# probatio_base.net
KiCad netlist of a schematic drawn in EAGLE
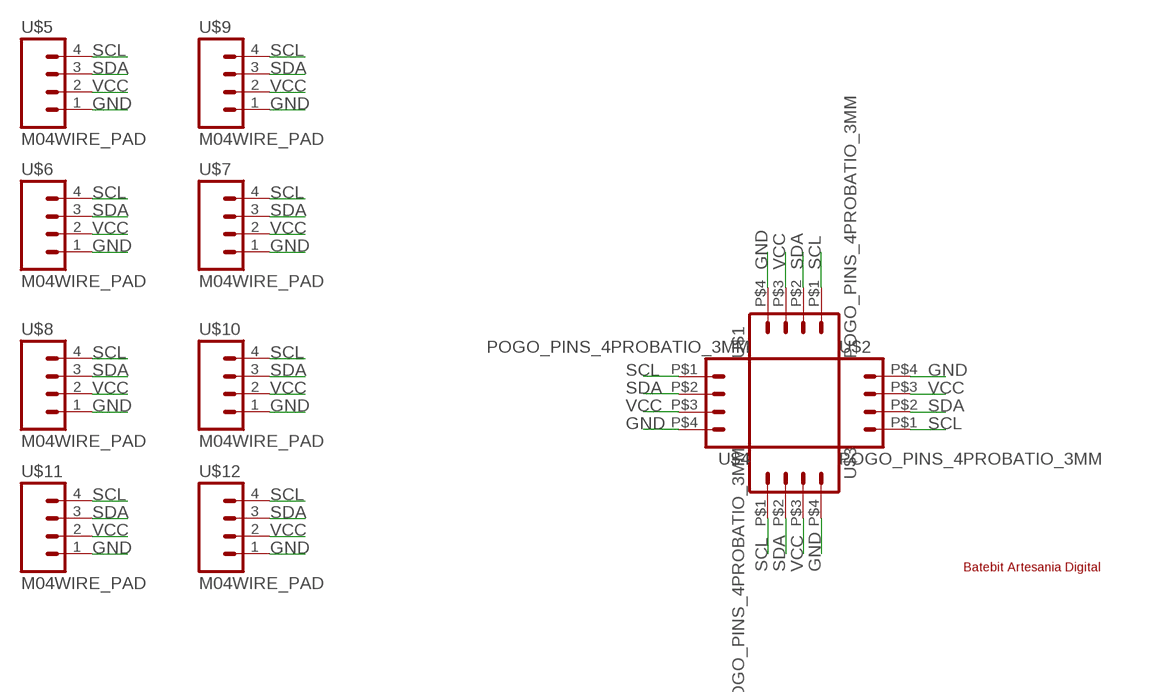
[diagram p0: schematic, sheet 1]

(export (version "E")
  (design (tool "Eeschema 10.0.6"))
  (components
    (comp (ref "U$1")
      (value "POGO_PINS_4PROBATIO_3MM")
      (footprint "eagle-import:POGO-PINS-4")
      (libsource (lib "eagle-import") (part "POGO_PINS_4PROBATIO_3MM"))
    )
    (comp (ref "U$2")
      (value "POGO_PINS_4PROBATIO_3MM")
      (footprint "eagle-import:POGO-PINS-4")
      (libsource (lib "eagle-import") (part "POGO_PINS_4PROBATIO_3MM"))
    )
    (comp (ref "U$3")
      (value "POGO_PINS_4PROBATIO_3MM")
      (footprint "eagle-import:POGO-PINS-4")
      (libsource (lib "eagle-import") (part "POGO_PINS_4PROBATIO_3MM"))
    )
    (comp (ref "U$4")
      (value "POGO_PINS_4PROBATIO_3MM")
      (footprint "eagle-import:POGO-PINS-4")
      (libsource (lib "eagle-import") (part "POGO_PINS_4PROBATIO_3MM"))
    )
    (comp (ref "U$5")
      (value "M04WIRE_PAD")
      (footprint "eagle-import:1X04_SMD")
      (libsource (lib "eagle-import") (part "M04WIRE_PAD"))
    )
    (comp (ref "U$6")
      (value "M04WIRE_PAD")
      (footprint "eagle-import:1X04_SMD")
      (libsource (lib "eagle-import") (part "M04WIRE_PAD"))
    )
    (comp (ref "U$7")
      (value "M04WIRE_PAD")
      (footprint "eagle-import:1X04_SMD")
      (libsource (lib "eagle-import") (part "M04WIRE_PAD"))
    )
    (comp (ref "U$8")
      (value "M04WIRE_PAD")
      (footprint "eagle-import:1X04_SMD")
      (libsource (lib "eagle-import") (part "M04WIRE_PAD"))
    )
    (comp (ref "U$9")
      (value "M04WIRE_PAD")
      (footprint "eagle-import:1X04_SMD")
      (libsource (lib "eagle-import") (part "M04WIRE_PAD"))
    )
    (comp (ref "U$10")
      (value "M04WIRE_PAD")
      (footprint "eagle-import:1X04_SMD")
      (libsource (lib "eagle-import") (part "M04WIRE_PAD"))
    )
    (comp (ref "U$11")
      (value "M04WIRE_PAD")
      (footprint "eagle-import:1X04_SMD")
      (libsource (lib "eagle-import") (part "M04WIRE_PAD"))
    )
    (comp (ref "U$12")
      (value "M04WIRE_PAD")
      (footprint "eagle-import:1X04_SMD")
      (libsource (lib "eagle-import") (part "M04WIRE_PAD"))
    )
    (comp (ref "U$13")
      (value "BATEBIT_PEQ")
      (footprint "eagle-import:BATEBIT_PEQ")
      (libsource (lib "eagle-import") (part "BATEBIT_PEQ"))
    )
  )
  (nets
    (net (code "1") (name "/GND") (class "Default")
      (node (ref "U$1") (pin "P$4") (pinfunction "4_P$4") (pintype "passive"))
      (node (ref "U$10") (pin "1") (pinfunction "1_1") (pintype "passive"))
      (node (ref "U$11") (pin "1") (pinfunction "1_1") (pintype "passive"))
      (node (ref "U$12") (pin "1") (pinfunction "1_1") (pintype "passive"))
      (node (ref "U$2") (pin "P$4") (pinfunction "4_P$4") (pintype "passive"))
      (node (ref "U$3") (pin "P$4") (pinfunction "4_P$4") (pintype "passive"))
      (node (ref "U$4") (pin "P$4") (pinfunction "4_P$4") (pintype "passive"))
      (node (ref "U$5") (pin "1") (pinfunction "1_1") (pintype "passive"))
      (node (ref "U$6") (pin "1") (pinfunction "1_1") (pintype "passive"))
      (node (ref "U$7") (pin "1") (pinfunction "1_1") (pintype "passive"))
      (node (ref "U$8") (pin "1") (pinfunction "1_1") (pintype "passive"))
      (node (ref "U$9") (pin "1") (pinfunction "1_1") (pintype "passive"))
    )
    (net (code "2") (name "/SCL") (class "Default")
      (node (ref "U$1") (pin "P$1") (pinfunction "1_P$1") (pintype "passive"))
      (node (ref "U$10") (pin "4") (pinfunction "4_4") (pintype "passive"))
      (node (ref "U$11") (pin "4") (pinfunction "4_4") (pintype "passive"))
      (node (ref "U$12") (pin "4") (pinfunction "4_4") (pintype "passive"))
      (node (ref "U$2") (pin "P$1") (pinfunction "1_P$1") (pintype "passive"))
      (node (ref "U$3") (pin "P$1") (pinfunction "1_P$1") (pintype "passive"))
      (node (ref "U$4") (pin "P$1") (pinfunction "1_P$1") (pintype "passive"))
      (node (ref "U$5") (pin "4") (pinfunction "4_4") (pintype "passive"))
      (node (ref "U$6") (pin "4") (pinfunction "4_4") (pintype "passive"))
      (node (ref "U$7") (pin "4") (pinfunction "4_4") (pintype "passive"))
      (node (ref "U$8") (pin "4") (pinfunction "4_4") (pintype "passive"))
      (node (ref "U$9") (pin "4") (pinfunction "4_4") (pintype "passive"))
    )
    (net (code "3") (name "/SDA") (class "Default")
      (node (ref "U$1") (pin "P$2") (pinfunction "2_P$2") (pintype "passive"))
      (node (ref "U$10") (pin "3") (pinfunction "3_3") (pintype "passive"))
      (node (ref "U$11") (pin "3") (pinfunction "3_3") (pintype "passive"))
      (node (ref "U$12") (pin "3") (pinfunction "3_3") (pintype "passive"))
      (node (ref "U$2") (pin "P$2") (pinfunction "2_P$2") (pintype "passive"))
      (node (ref "U$3") (pin "P$2") (pinfunction "2_P$2") (pintype "passive"))
      (node (ref "U$4") (pin "P$2") (pinfunction "2_P$2") (pintype "passive"))
      (node (ref "U$5") (pin "3") (pinfunction "3_3") (pintype "passive"))
      (node (ref "U$6") (pin "3") (pinfunction "3_3") (pintype "passive"))
      (node (ref "U$7") (pin "3") (pinfunction "3_3") (pintype "passive"))
      (node (ref "U$8") (pin "3") (pinfunction "3_3") (pintype "passive"))
      (node (ref "U$9") (pin "3") (pinfunction "3_3") (pintype "passive"))
    )
    (net (code "4") (name "/VCC") (class "Default")
      (node (ref "U$1") (pin "P$3") (pinfunction "3_P$3") (pintype "passive"))
      (node (ref "U$10") (pin "2") (pinfunction "2_2") (pintype "passive"))
      (node (ref "U$11") (pin "2") (pinfunction "2_2") (pintype "passive"))
      (node (ref "U$12") (pin "2") (pinfunction "2_2") (pintype "passive"))
      (node (ref "U$2") (pin "P$3") (pinfunction "3_P$3") (pintype "passive"))
      (node (ref "U$3") (pin "P$3") (pinfunction "3_P$3") (pintype "passive"))
      (node (ref "U$4") (pin "P$3") (pinfunction "3_P$3") (pintype "passive"))
      (node (ref "U$5") (pin "2") (pinfunction "2_2") (pintype "passive"))
      (node (ref "U$6") (pin "2") (pinfunction "2_2") (pintype "passive"))
      (node (ref "U$7") (pin "2") (pinfunction "2_2") (pintype "passive"))
      (node (ref "U$8") (pin "2") (pinfunction "2_2") (pintype "passive"))
      (node (ref "U$9") (pin "2") (pinfunction "2_2") (pintype "passive"))
    )
  )
)
